# USB_Hub.net
KiCad netlist of a schematic drawn in EasyEDA Pro
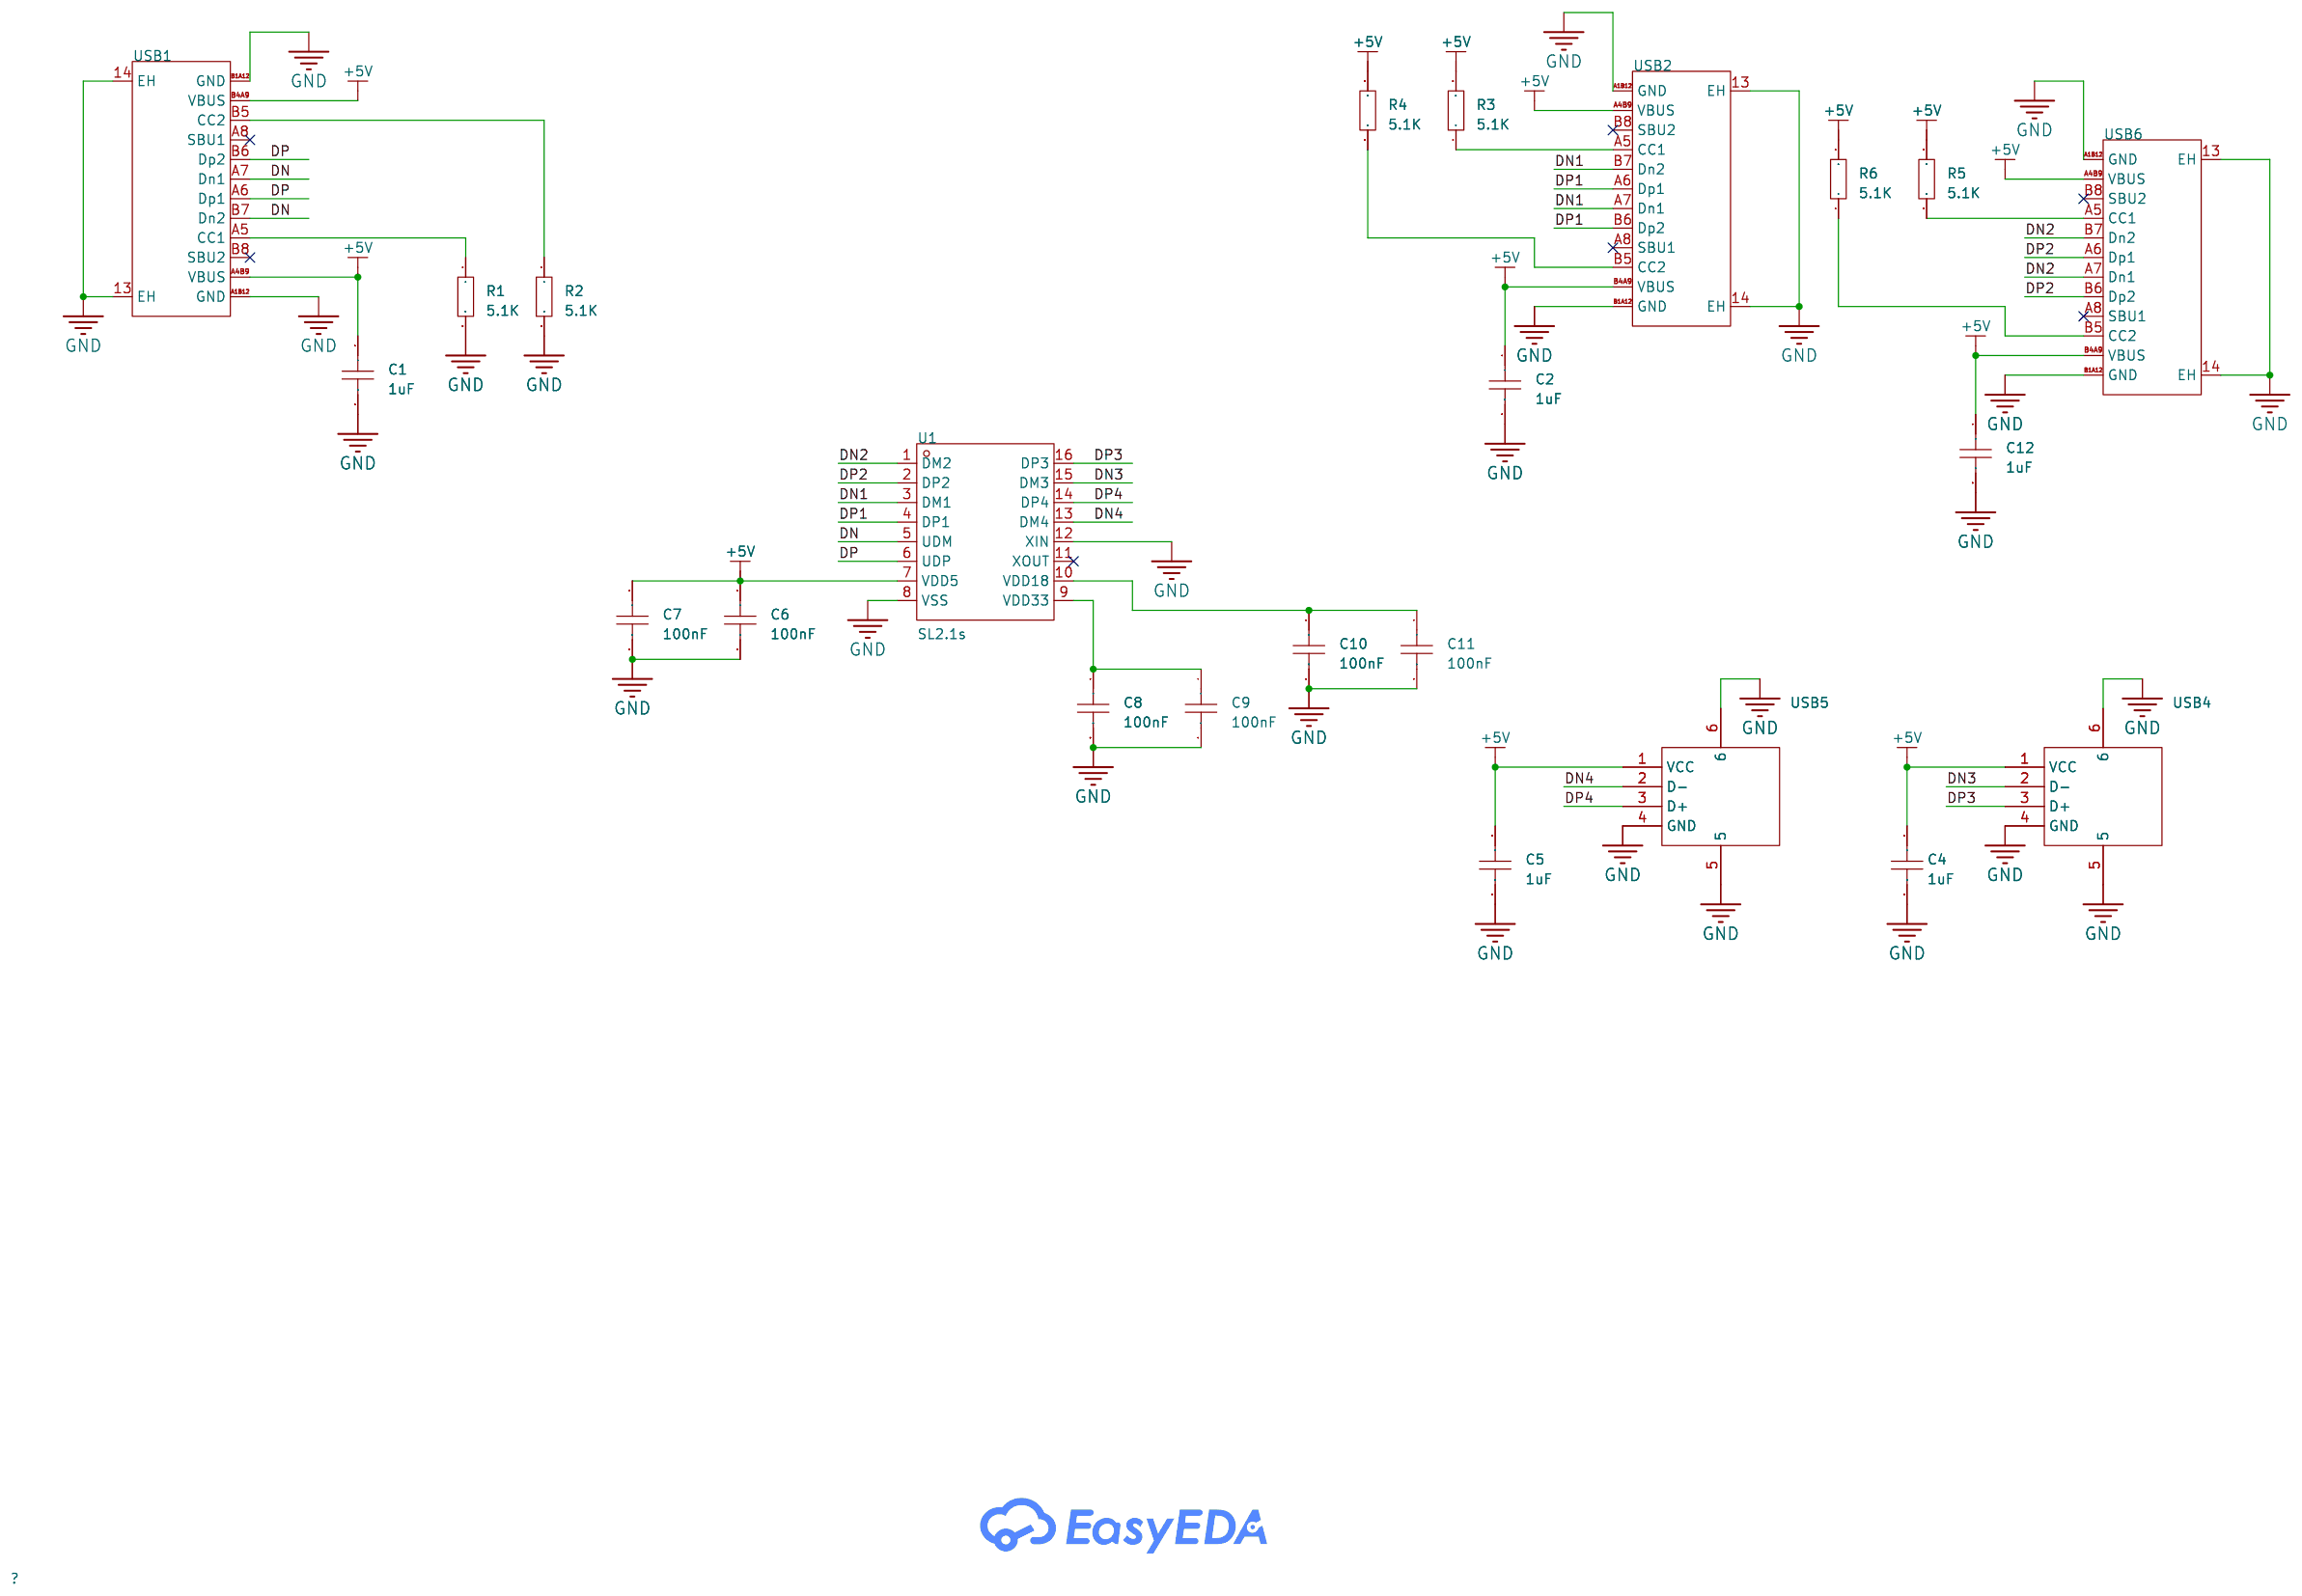
[diagram p0: schematic sheet]

(export (version "E")
  (design (tool "Eeschema 10.0.6"))
  (components
    (comp (ref "C1") (value "1uF") (footprint "easyedapro:C0603") (libsource (lib "easyedapro") (part "CAP")))
    (comp (ref "C2") (value "1uF") (footprint "easyedapro:C0603") (libsource (lib "easyedapro") (part "CAP")))
    (comp (ref "C4") (value "1uF") (footprint "easyedapro:C0603") (libsource (lib "easyedapro") (part "CAP")))
    (comp (ref "C5") (value "1uF") (footprint "easyedapro:C0603") (libsource (lib "easyedapro") (part "CAP")))
    (comp (ref "C6")
      (value "100nF")
      (footprint "easyedapro:C0603")
      (libsource (lib "easyedapro") (part "CAP"))
    )
    (comp (ref "C7")
      (value "100nF")
      (footprint "easyedapro:C0603")
      (libsource (lib "easyedapro") (part "CAP"))
    )
    (comp (ref "C8")
      (value "100nF")
      (footprint "easyedapro:C0603")
      (libsource (lib "easyedapro") (part "CAP"))
    )
    (comp (ref "C9")
      (value "100nF")
      (footprint "easyedapro:C0603")
      (libsource (lib "easyedapro") (part "CAP"))
    )
    (comp (ref "C10")
      (value "100nF")
      (footprint "easyedapro:C0603")
      (libsource (lib "easyedapro") (part "CAP"))
    )
    (comp (ref "C11")
      (value "100nF")
      (footprint "easyedapro:C0603")
      (libsource (lib "easyedapro") (part "CAP"))
    )
    (comp (ref "C12")
      (value "1uF")
      (footprint "easyedapro:C0603")
      (libsource (lib "easyedapro") (part "CAP"))
    )
    (comp (ref "R1")
      (value "5.1K")
      (footprint "easyedapro:R0603")
      (libsource (lib "easyedapro") (part "Res"))
    )
    (comp (ref "R2")
      (value "5.1K")
      (footprint "easyedapro:R0603")
      (libsource (lib "easyedapro") (part "Res"))
    )
    (comp (ref "R3")
      (value "5.1K")
      (footprint "easyedapro:R0603")
      (libsource (lib "easyedapro") (part "Res"))
    )
    (comp (ref "R4")
      (value "5.1K")
      (footprint "easyedapro:R0603")
      (libsource (lib "easyedapro") (part "Res"))
    )
    (comp (ref "R5")
      (value "5.1K")
      (footprint "easyedapro:R0603")
      (libsource (lib "easyedapro") (part "Res"))
    )
    (comp (ref "R6")
      (value "5.1K")
      (footprint "easyedapro:R0603")
      (libsource (lib "easyedapro") (part "Res"))
    )
    (comp (ref "U1")
      (value "SL2.1s")
      (footprint "easyedapro:SSOP-16_L4.6-W2.6-P0.53-LS4.0-BL")
      (fields (field (name "Manufacturer") "CoreChips(和芯润德)"))
      (libsource (lib "easyedapro") (part "SL2.1S"))
    )
    (comp (ref "USB1")
      (value "TYPE-C 16PIN 2MD(073)")
      (footprint "easyedapro:USB-C-SMD_TYPE-C-16PIN-2MD-073")
      (fields (field (name "Manufacturer") "SHOU HAN(首韩)"))
      (libsource (lib "easyedapro") (part "TYPE-C 16PIN 2MD(073)"))
    )
    (comp (ref "USB2")
      (value "TYPE-C 16PIN 2MD(073)")
      (footprint "easyedapro:USB-C-SMD_TYPE-C-16PIN-2MD-073")
      (fields (field (name "Manufacturer") "SHOU HAN(首韩)"))
      (libsource (lib "easyedapro") (part "TYPE-C 16PIN 2MD(073)"))
    )
    (comp (ref "USB4")
      (value "10.0 QHHTZB6.3")
      (footprint "easyedapro:USB-A-TH_10.0QHHTZB6.3")
      (fields (field (name "Manufacturer") "SHOU HAN(首韩)"))
      (libsource (lib "easyedapro") (part "10.0 QHHTZB6.3"))
    )
    (comp (ref "USB5")
      (value "10.0 QHHTZB6.3")
      (footprint "easyedapro:USB-A-TH_10.0QHHTZB6.3")
      (fields (field (name "Manufacturer") "SHOU HAN(首韩)"))
      (libsource (lib "easyedapro") (part "10.0 QHHTZB6.3"))
    )
    (comp (ref "USB6")
      (value "TYPE-C 16PIN 2MD(073)")
      (footprint "easyedapro:USB-C-SMD_TYPE-C-16PIN-2MD-073")
      (fields (field (name "Manufacturer") "SHOU HAN(首韩)"))
      (libsource (lib "easyedapro") (part "TYPE-C 16PIN 2MD(073)"))
    )
  )
  (nets
    (net (code "1") (name "+5V") (class "Default")
      (node (ref "C1") (pin "1") (pinfunction "1_1") (pintype "input"))
      (node (ref "C12") (pin "1") (pinfunction "1_1") (pintype "input"))
      (node (ref "C2") (pin "1") (pinfunction "1_1") (pintype "input"))
      (node (ref "C4") (pin "1") (pinfunction "1_1") (pintype "input"))
      (node (ref "C5") (pin "1") (pinfunction "1_1") (pintype "input"))
      (node (ref "C6") (pin "1") (pinfunction "1_1") (pintype "input"))
      (node (ref "C7") (pin "1") (pinfunction "1_1") (pintype "input"))
      (node (ref "R3") (pin "2") (pinfunction "2_2") (pintype "input"))
      (node (ref "R4") (pin "2") (pinfunction "2_2") (pintype "input"))
      (node (ref "R5") (pin "2") (pinfunction "2_2") (pintype "input"))
      (node (ref "R6") (pin "2") (pinfunction "2_2") (pintype "input"))
      (node (ref "U1") (pin "7") (pinfunction "VDD5_7") (pintype "unspecified"))
      (node (ref "USB1") (pin "A4B9") (pinfunction "VBUS_A4B9") (pintype "unspecified"))
      (node (ref "USB1") (pin "B4A9") (pinfunction "VBUS_B4A9") (pintype "unspecified"))
      (node (ref "USB2") (pin "A4B9") (pinfunction "VBUS_A4B9") (pintype "unspecified"))
      (node (ref "USB2") (pin "B4A9") (pinfunction "VBUS_B4A9") (pintype "unspecified"))
      (node (ref "USB4") (pin "1") (pinfunction "VCC_1") (pintype "unspecified"))
      (node (ref "USB5") (pin "1") (pinfunction "VCC_1") (pintype "unspecified"))
      (node (ref "USB6") (pin "A4B9") (pinfunction "VBUS_A4B9") (pintype "unspecified"))
      (node (ref "USB6") (pin "B4A9") (pinfunction "VBUS_B4A9") (pintype "unspecified"))
    )
    (net (code "2") (name "/DN") (class "Default")
      (node (ref "U1") (pin "5") (pinfunction "UDM_5") (pintype "unspecified"))
      (node (ref "USB1") (pin "A7") (pinfunction "Dn1_A7") (pintype "unspecified"))
      (node (ref "USB1") (pin "B7") (pinfunction "Dn2_B7") (pintype "unspecified"))
    )
    (net (code "3") (name "/DN1") (class "Default")
      (node (ref "U1") (pin "3") (pinfunction "DM1_3") (pintype "unspecified"))
      (node (ref "USB2") (pin "A7") (pinfunction "Dn1_A7") (pintype "unspecified"))
      (node (ref "USB2") (pin "B7") (pinfunction "Dn2_B7") (pintype "unspecified"))
    )
    (net (code "4") (name "/DN2") (class "Default")
      (node (ref "U1") (pin "1") (pinfunction "DM2_1") (pintype "unspecified"))
      (node (ref "USB6") (pin "A7") (pinfunction "Dn1_A7") (pintype "unspecified"))
      (node (ref "USB6") (pin "B7") (pinfunction "Dn2_B7") (pintype "unspecified"))
    )
    (net (code "5") (name "/DN3") (class "Default")
      (node (ref "U1") (pin "15") (pinfunction "DM3_15") (pintype "unspecified"))
      (node (ref "USB4") (pin "2") (pinfunction "D-_2") (pintype "unspecified"))
    )
    (net (code "6") (name "/DN4") (class "Default")
      (node (ref "U1") (pin "13") (pinfunction "DM4_13") (pintype "unspecified"))
      (node (ref "USB5") (pin "2") (pinfunction "D-_2") (pintype "unspecified"))
    )
    (net (code "7") (name "/DP") (class "Default")
      (node (ref "U1") (pin "6") (pinfunction "UDP_6") (pintype "unspecified"))
      (node (ref "USB1") (pin "A6") (pinfunction "Dp1_A6") (pintype "unspecified"))
      (node (ref "USB1") (pin "B6") (pinfunction "Dp2_B6") (pintype "unspecified"))
    )
    (net (code "8") (name "/DP1") (class "Default")
      (node (ref "U1") (pin "4") (pinfunction "DP1_4") (pintype "unspecified"))
      (node (ref "USB2") (pin "A6") (pinfunction "Dp1_A6") (pintype "unspecified"))
      (node (ref "USB2") (pin "B6") (pinfunction "Dp2_B6") (pintype "unspecified"))
    )
    (net (code "9") (name "/DP2") (class "Default")
      (node (ref "U1") (pin "2") (pinfunction "DP2_2") (pintype "unspecified"))
      (node (ref "USB6") (pin "A6") (pinfunction "Dp1_A6") (pintype "unspecified"))
      (node (ref "USB6") (pin "B6") (pinfunction "Dp2_B6") (pintype "unspecified"))
    )
    (net (code "10") (name "/DP3") (class "Default")
      (node (ref "U1") (pin "16") (pinfunction "DP3_16") (pintype "unspecified"))
      (node (ref "USB4") (pin "3") (pinfunction "D+_3") (pintype "unspecified"))
    )
    (net (code "11") (name "/DP4") (class "Default")
      (node (ref "U1") (pin "14") (pinfunction "DP4_14") (pintype "unspecified"))
      (node (ref "USB5") (pin "3") (pinfunction "D+_3") (pintype "unspecified"))
    )
    (net (code "12") (name "GND") (class "Default")
      (node (ref "C1") (pin "2") (pinfunction "2_2") (pintype "input"))
      (node (ref "C10") (pin "2") (pinfunction "2_2") (pintype "input"))
      (node (ref "C11") (pin "2") (pinfunction "2_2") (pintype "input"))
      (node (ref "C12") (pin "2") (pinfunction "2_2") (pintype "input"))
      (node (ref "C2") (pin "2") (pinfunction "2_2") (pintype "input"))
      (node (ref "C4") (pin "2") (pinfunction "2_2") (pintype "input"))
      (node (ref "C5") (pin "2") (pinfunction "2_2") (pintype "input"))
      (node (ref "C6") (pin "2") (pinfunction "2_2") (pintype "input"))
      (node (ref "C7") (pin "2") (pinfunction "2_2") (pintype "input"))
      (node (ref "C8") (pin "2") (pinfunction "2_2") (pintype "input"))
      (node (ref "C9") (pin "2") (pinfunction "2_2") (pintype "input"))
      (node (ref "R1") (pin "2") (pinfunction "2_2") (pintype "input"))
      (node (ref "R2") (pin "2") (pinfunction "2_2") (pintype "input"))
      (node (ref "U1") (pin "12") (pinfunction "XIN_12") (pintype "unspecified"))
      (node (ref "U1") (pin "8") (pinfunction "VSS_8") (pintype "unspecified"))
      (node (ref "USB1") (pin "13") (pinfunction "EH_13") (pintype "unspecified"))
      (node (ref "USB1") (pin "14") (pinfunction "EH_14") (pintype "unspecified"))
      (node (ref "USB1") (pin "A1B12") (pinfunction "GND_A1B12") (pintype "unspecified"))
      (node (ref "USB1") (pin "B1A12") (pinfunction "GND_B1A12") (pintype "unspecified"))
      (node (ref "USB2") (pin "13") (pinfunction "EH_13") (pintype "unspecified"))
      (node (ref "USB2") (pin "14") (pinfunction "EH_14") (pintype "unspecified"))
      (node (ref "USB2") (pin "A1B12") (pinfunction "GND_A1B12") (pintype "unspecified"))
      (node (ref "USB2") (pin "B1A12") (pinfunction "GND_B1A12") (pintype "unspecified"))
      (node (ref "USB4") (pin "4") (pinfunction "GND_4") (pintype "unspecified"))
      (node (ref "USB4") (pin "5") (pinfunction "5_5") (pintype "unspecified"))
      (node (ref "USB4") (pin "6") (pinfunction "6_6") (pintype "unspecified"))
      (node (ref "USB5") (pin "4") (pinfunction "GND_4") (pintype "unspecified"))
      (node (ref "USB5") (pin "5") (pinfunction "5_5") (pintype "unspecified"))
      (node (ref "USB5") (pin "6") (pinfunction "6_6") (pintype "unspecified"))
      (node (ref "USB6") (pin "13") (pinfunction "EH_13") (pintype "unspecified"))
      (node (ref "USB6") (pin "14") (pinfunction "EH_14") (pintype "unspecified"))
      (node (ref "USB6") (pin "A1B12") (pinfunction "GND_A1B12") (pintype "unspecified"))
      (node (ref "USB6") (pin "B1A12") (pinfunction "GND_B1A12") (pintype "unspecified"))
    )
    (net (code "13") (name "Net-(U1-VDD18)") (class "Default")
      (node (ref "C10") (pin "1") (pinfunction "1_1") (pintype "input"))
      (node (ref "C11") (pin "1") (pinfunction "1_1") (pintype "input"))
      (node (ref "U1") (pin "10") (pinfunction "VDD18_10") (pintype "unspecified"))
    )
    (net (code "14") (name "Net-(U1-VDD33)") (class "Default")
      (node (ref "C8") (pin "1") (pinfunction "1_1") (pintype "input"))
      (node (ref "C9") (pin "1") (pinfunction "1_1") (pintype "input"))
      (node (ref "U1") (pin "9") (pinfunction "VDD33_9") (pintype "unspecified"))
    )
    (net (code "15") (name "Net-(USB1-CC1)") (class "Default")
      (node (ref "R1") (pin "1") (pinfunction "1_1") (pintype "input"))
      (node (ref "USB1") (pin "A5") (pinfunction "CC1_A5") (pintype "unspecified"))
    )
    (net (code "16") (name "Net-(USB1-CC2)") (class "Default")
      (node (ref "R2") (pin "1") (pinfunction "1_1") (pintype "input"))
      (node (ref "USB1") (pin "B5") (pinfunction "CC2_B5") (pintype "unspecified"))
    )
    (net (code "17") (name "Net-(USB2-CC1)") (class "Default")
      (node (ref "R3") (pin "1") (pinfunction "1_1") (pintype "input"))
      (node (ref "USB2") (pin "A5") (pinfunction "CC1_A5") (pintype "unspecified"))
    )
    (net (code "18") (name "Net-(USB2-CC2)") (class "Default")
      (node (ref "R4") (pin "1") (pinfunction "1_1") (pintype "input"))
      (node (ref "USB2") (pin "B5") (pinfunction "CC2_B5") (pintype "unspecified"))
    )
    (net (code "19") (name "Net-(USB6-CC1)") (class "Default")
      (node (ref "R5") (pin "1") (pinfunction "1_1") (pintype "input"))
      (node (ref "USB6") (pin "A5") (pinfunction "CC1_A5") (pintype "unspecified"))
    )
    (net (code "20") (name "Net-(USB6-CC2)") (class "Default")
      (node (ref "R6") (pin "1") (pinfunction "1_1") (pintype "input"))
      (node (ref "USB6") (pin "B5") (pinfunction "CC2_B5") (pintype "unspecified"))
    )
    (net (code "21") (name "unconnected-(U1-XOUT-Pad11)") (class "Default")
      (node (ref "U1") (pin "11") (pinfunction "XOUT_11") (pintype "unspecified+no_connect"))
    )
    (net (code "22") (name "unconnected-(USB1-SBU1-PadA8)") (class "Default")
      (node (ref "USB1") (pin "A8") (pinfunction "SBU1_A8") (pintype "unspecified+no_connect"))
    )
    (net (code "23") (name "unconnected-(USB1-SBU2-PadB8)") (class "Default")
      (node (ref "USB1") (pin "B8") (pinfunction "SBU2_B8") (pintype "unspecified+no_connect"))
    )
    (net (code "24") (name "unconnected-(USB2-SBU1-PadA8)") (class "Default")
      (node (ref "USB2") (pin "A8") (pinfunction "SBU1_A8") (pintype "unspecified+no_connect"))
    )
    (net (code "25") (name "unconnected-(USB2-SBU2-PadB8)") (class "Default")
      (node (ref "USB2") (pin "B8") (pinfunction "SBU2_B8") (pintype "unspecified+no_connect"))
    )
    (net (code "26") (name "unconnected-(USB6-SBU1-PadA8)") (class "Default")
      (node (ref "USB6") (pin "A8") (pinfunction "SBU1_A8") (pintype "unspecified+no_connect"))
    )
    (net (code "27") (name "unconnected-(USB6-SBU2-PadB8)") (class "Default")
      (node (ref "USB6") (pin "B8") (pinfunction "SBU2_B8") (pintype "unspecified+no_connect"))
    )
  )
)
